# RFM69PI.net
KiCad netlist of a schematic drawn in EAGLE
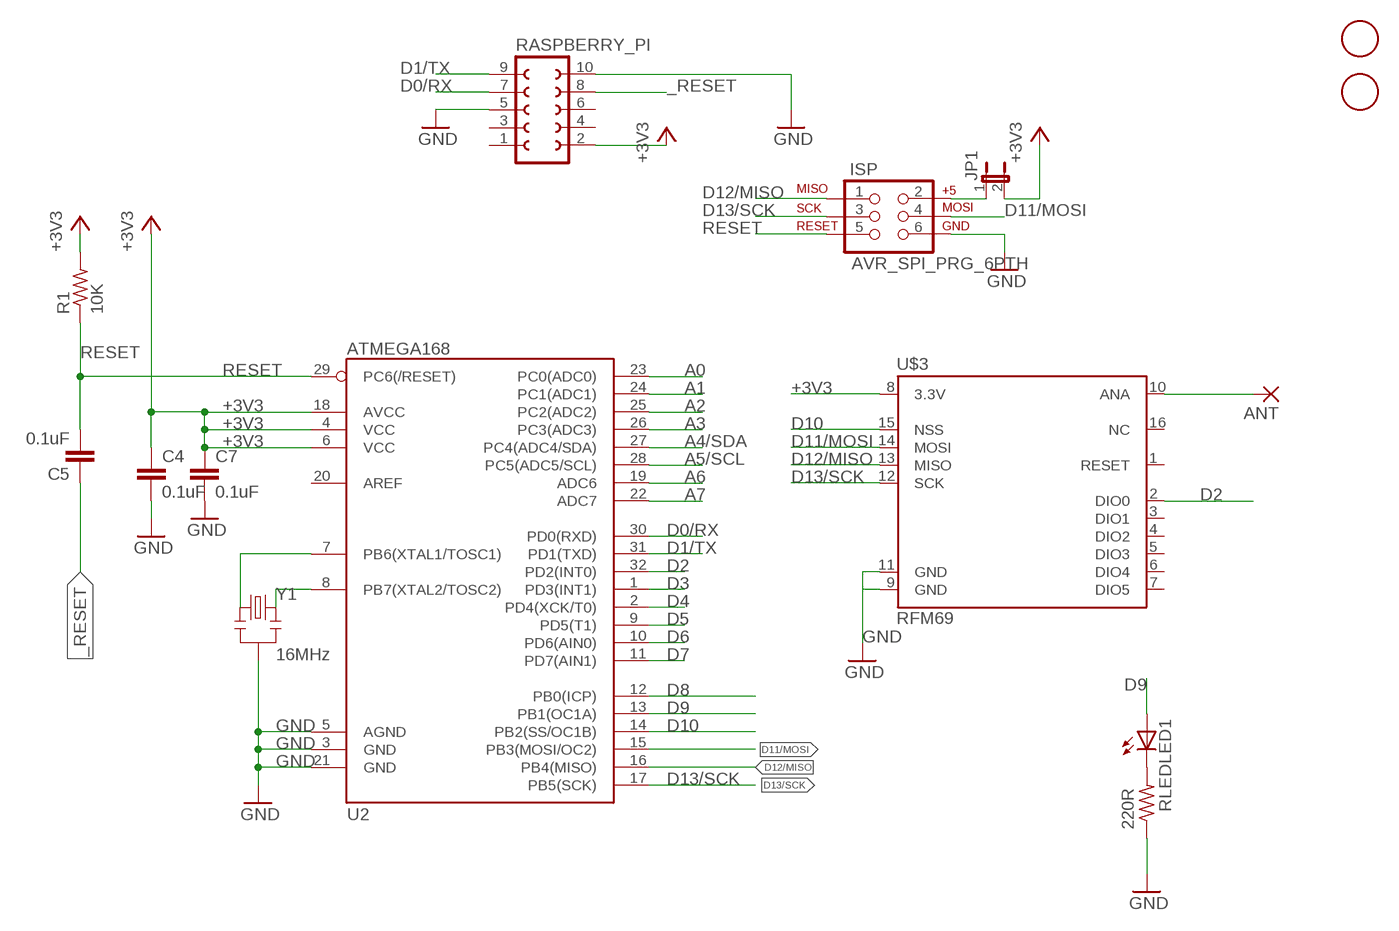
[diagram p0: schematic, sheet 1]

(export (version "E")
  (design (tool "Eeschema 10.0.6"))
  (components
    (comp (ref "ANT")
      (value "1,6/0,8")
      (footprint "eagle-import:1,6_0,8")
      (libsource (lib "eagle-import") (part "1,6/0,8"))
    )
    (comp (ref "C4")
      (value "0.1uF")
      (footprint "eagle-import:C0805")
      (libsource (lib "eagle-import") (part "C-EUC0805"))
    )
    (comp (ref "C5")
      (value "0.1uF")
      (footprint "eagle-import:C0805")
      (libsource (lib "eagle-import") (part "C-EUC0805"))
    )
    (comp (ref "C7")
      (value "0.1uF")
      (footprint "eagle-import:C0805")
      (libsource (lib "eagle-import") (part "resistor_C-EUC0805"))
    )
    (comp (ref "ISP")
      (value "AVR_SPI_PRG_6PTH")
      (footprint "eagle-import:2X3")
      (libsource (lib "eagle-import") (part "AVR_SPI_PRG_6PTH"))
    )
    (comp (ref "JP1")
      (value "JUMPER-2PTH")
      (footprint "eagle-import:1X02")
      (libsource (lib "eagle-import") (part "JUMPER-2PTH"))
    )
    (comp (ref "LED1")
      (value "LEDSML0805")
      (footprint "eagle-import:SML0805")
      (libsource (lib "eagle-import") (part "LEDSML0805"))
    )
    (comp (ref "R1")
      (value "10K")
      (footprint "eagle-import:R0805")
      (libsource (lib "eagle-import") (part "R-US_R0805"))
    )
    (comp (ref "RASPBERRY_PI")
      (value "FE05-2")
      (footprint "eagle-import:FE05-2")
      (libsource (lib "eagle-import") (part "FE05-2"))
    )
    (comp (ref "RLED")
      (value "220R")
      (footprint "eagle-import:R0805")
      (libsource (lib "eagle-import") (part "R-US_R0805"))
    )
    (comp (ref "U$1")
      (value "FIDUCIAL")
      (footprint "eagle-import:FIDUCIAL_1MM")
      (libsource (lib "eagle-import") (part "FIDUCIAL"))
    )
    (comp (ref "U$2")
      (value "FIDUCIAL")
      (footprint "eagle-import:FIDUCIAL_1MM")
      (libsource (lib "eagle-import") (part "FIDUCIAL"))
    )
    (comp (ref "U$3")
      (value "RFM69")
      (footprint "eagle-import:RFM69SMD")
      (libsource (lib "eagle-import") (part "RFM69"))
    )
    (comp (ref "U2")
      (value "ATMEGA168")
      (footprint "eagle-import:TQFP32-08")
      (libsource (lib "eagle-import") (part "ATMEGA168"))
    )
    (comp (ref "Y1")
      (value "16MHz")
      (footprint "eagle-import:RESONATOR-SMD")
      (libsource (lib "eagle-import") (part "RESONATOR16MHZ"))
    )
  )
  (nets
    (net (code "1") (name "+3V3") (class "Default")
      (node (ref "C4") (pin "1") (pinfunction "1_1") (pintype "passive"))
      (node (ref "C7") (pin "1") (pinfunction "1_1") (pintype "passive"))
      (node (ref "JP1") (pin "2") (pinfunction "2_2") (pintype "passive"))
      (node (ref "R1") (pin "2") (pinfunction "2_2") (pintype "passive"))
      (node (ref "RASPBERRY_PI") (pin "2") (pinfunction "2_2") (pintype "passive"))
      (node (ref "U$3") (pin "8") (pinfunction "3.3V_8") (pintype "power_in"))
      (node (ref "U2") (pin "18") (pinfunction "AVCC_18") (pintype "bidirectional"))
      (node (ref "U2") (pin "4") (pinfunction "VCC_4") (pintype "bidirectional"))
      (node (ref "U2") (pin "6") (pinfunction "VCC_6") (pintype "bidirectional"))
    )
    (net (code "2") (name "/A0") (class "Default")
      (node (ref "U2") (pin "23") (pinfunction "PC0(ADC0)_23") (pintype "bidirectional"))
    )
    (net (code "3") (name "/A1") (class "Default")
      (node (ref "U2") (pin "24") (pinfunction "PC1(ADC1)_24") (pintype "bidirectional"))
    )
    (net (code "4") (name "/A2") (class "Default")
      (node (ref "U2") (pin "25") (pinfunction "PC2(ADC2)_25") (pintype "bidirectional"))
    )
    (net (code "5") (name "/A3") (class "Default")
      (node (ref "U2") (pin "26") (pinfunction "PC3(ADC3)_26") (pintype "bidirectional"))
    )
    (net (code "6") (name "/A4{slash}SDA") (class "Default")
      (node (ref "U2") (pin "27") (pinfunction "PC4(ADC4/SDA)_27") (pintype "bidirectional"))
    )
    (net (code "7") (name "/A5{slash}SCL") (class "Default")
      (node (ref "U2") (pin "28") (pinfunction "PC5(ADC5/SCL)_28") (pintype "bidirectional"))
    )
    (net (code "8") (name "/A6") (class "Default")
      (node (ref "U2") (pin "19") (pinfunction "ADC6_19") (pintype "bidirectional"))
    )
    (net (code "9") (name "/A7") (class "Default")
      (node (ref "U2") (pin "22") (pinfunction "ADC7_22") (pintype "bidirectional"))
    )
    (net (code "10") (name "/D0{slash}RX") (class "Default")
      (node (ref "RASPBERRY_PI") (pin "7") (pinfunction "7_7") (pintype "passive"))
      (node (ref "U2") (pin "30") (pinfunction "PD0(RXD)_30") (pintype "bidirectional"))
    )
    (net (code "11") (name "/D1{slash}TX") (class "Default")
      (node (ref "RASPBERRY_PI") (pin "9") (pinfunction "9_9") (pintype "passive"))
      (node (ref "U2") (pin "31") (pinfunction "PD1(TXD)_31") (pintype "bidirectional"))
    )
    (net (code "12") (name "/D2") (class "Default")
      (node (ref "U$3") (pin "2") (pinfunction "DIO0_2") (pintype "bidirectional"))
      (node (ref "U2") (pin "32") (pinfunction "PD2(INT0)_32") (pintype "bidirectional"))
    )
    (net (code "13") (name "/D3") (class "Default")
      (node (ref "U2") (pin "1") (pinfunction "PD3(INT1)_1") (pintype "bidirectional"))
    )
    (net (code "14") (name "/D4") (class "Default")
      (node (ref "U2") (pin "2") (pinfunction "PD4(XCK/T0)_2") (pintype "bidirectional"))
    )
    (net (code "15") (name "/D5") (class "Default")
      (node (ref "U2") (pin "9") (pinfunction "PD5(T1)_9") (pintype "bidirectional"))
    )
    (net (code "16") (name "/D6") (class "Default")
      (node (ref "U2") (pin "10") (pinfunction "PD6(AIN0)_10") (pintype "bidirectional"))
    )
    (net (code "17") (name "/D7") (class "Default")
      (node (ref "U2") (pin "11") (pinfunction "PD7(AIN1)_11") (pintype "bidirectional"))
    )
    (net (code "18") (name "/D8") (class "Default")
      (node (ref "U2") (pin "12") (pinfunction "PB0(ICP)_12") (pintype "bidirectional"))
    )
    (net (code "19") (name "/D9") (class "Default")
      (node (ref "LED1") (pin "A") (pinfunction "A_A") (pintype "passive"))
      (node (ref "U2") (pin "13") (pinfunction "PB1(OC1A)_13") (pintype "bidirectional"))
    )
    (net (code "20") (name "/D10") (class "Default")
      (node (ref "U$3") (pin "15") (pinfunction "NSS_15") (pintype "input"))
      (node (ref "U2") (pin "14") (pinfunction "PB2(SS/OC1B)_14") (pintype "bidirectional"))
    )
    (net (code "21") (name "/NC") (class "Default")
      (node (ref "U$3") (pin "16") (pinfunction "NC_16") (pintype "power_in"))
    )
    (net (code "22") (name "/RESET") (class "Default")
      (node (ref "C5") (pin "2") (pinfunction "2_2") (pintype "passive"))
      (node (ref "ISP") (pin "5") (pinfunction "5_5") (pintype "passive"))
      (node (ref "R1") (pin "1") (pinfunction "1_1") (pintype "passive"))
      (node (ref "U2") (pin "29") (pinfunction "PC6(/RESET)_29") (pintype "bidirectional"))
    )
    (net (code "23") (name "D11{slash}MOSI") (class "Default")
      (node (ref "ISP") (pin "4") (pinfunction "4_4") (pintype "passive"))
      (node (ref "U$3") (pin "14") (pinfunction "MOSI_14") (pintype "input"))
      (node (ref "U2") (pin "15") (pinfunction "PB3(MOSI/OC2)_15") (pintype "bidirectional"))
    )
    (net (code "24") (name "D12{slash}MISO") (class "Default")
      (node (ref "ISP") (pin "1") (pinfunction "1_1") (pintype "passive"))
      (node (ref "U$3") (pin "13") (pinfunction "MISO_13") (pintype "output"))
      (node (ref "U2") (pin "16") (pinfunction "PB4(MISO)_16") (pintype "bidirectional"))
    )
    (net (code "25") (name "D13{slash}SCK") (class "Default")
      (node (ref "ISP") (pin "3") (pinfunction "3_3") (pintype "passive"))
      (node (ref "U$3") (pin "12") (pinfunction "SCK_12") (pintype "input"))
      (node (ref "U2") (pin "17") (pinfunction "PB5(SCK)_17") (pintype "bidirectional"))
    )
    (net (code "26") (name "GND") (class "Default")
      (node (ref "C4") (pin "2") (pinfunction "2_2") (pintype "passive"))
      (node (ref "C7") (pin "2") (pinfunction "2_2") (pintype "passive"))
      (node (ref "ISP") (pin "6") (pinfunction "6_6") (pintype "passive"))
      (node (ref "RASPBERRY_PI") (pin "10") (pinfunction "10_10") (pintype "passive"))
      (node (ref "RASPBERRY_PI") (pin "5") (pinfunction "5_5") (pintype "passive"))
      (node (ref "RLED") (pin "1") (pinfunction "1_1") (pintype "passive"))
      (node (ref "U$3") (pin "11") (pinfunction "GND_11") (pintype "power_in"))
      (node (ref "U$3") (pin "9") (pinfunction "GND_9") (pintype "power_in"))
      (node (ref "U2") (pin "21") (pinfunction "GND_21") (pintype "bidirectional"))
      (node (ref "U2") (pin "3") (pinfunction "GND_3") (pintype "bidirectional"))
      (node (ref "U2") (pin "5") (pinfunction "AGND_5") (pintype "bidirectional"))
      (node (ref "Y1") (pin "2") (pinfunction "2_2") (pintype "passive"))
    )
    (net (code "27") (name "Net-(ANT-P)") (class "Default")
      (node (ref "ANT") (pin "1") (pinfunction "P_1") (pintype "passive"))
      (node (ref "U$3") (pin "10") (pinfunction "ANA_10") (pintype "bidirectional"))
    )
    (net (code "28") (name "Net-(ISP-Pad2)") (class "Default")
      (node (ref "ISP") (pin "2") (pinfunction "2_2") (pintype "passive"))
      (node (ref "JP1") (pin "1") (pinfunction "1_1") (pintype "passive"))
    )
    (net (code "29") (name "Net-(LED1-PadC)") (class "Default")
      (node (ref "LED1") (pin "C") (pinfunction "C_C") (pintype "passive"))
      (node (ref "RLED") (pin "2") (pinfunction "2_2") (pintype "passive"))
    )
    (net (code "30") (name "Net-(U2-PB6(XTAL1{slash}TOSC1))") (class "Default")
      (node (ref "U2") (pin "7") (pinfunction "PB6(XTAL1/TOSC1)_7") (pintype "bidirectional"))
      (node (ref "Y1") (pin "1") (pinfunction "1_1") (pintype "passive"))
    )
    (net (code "31") (name "Net-(U2-PB7(XTAL2{slash}TOSC2))") (class "Default")
      (node (ref "U2") (pin "8") (pinfunction "PB7(XTAL2/TOSC2)_8") (pintype "bidirectional"))
      (node (ref "Y1") (pin "3") (pinfunction "3_3") (pintype "passive"))
    )
    (net (code "32") (name "_RESET") (class "Default")
      (node (ref "C5") (pin "1") (pinfunction "1_1") (pintype "passive"))
      (node (ref "RASPBERRY_PI") (pin "8") (pinfunction "8_8") (pintype "passive"))
    )
    (net (code "33") (name "unconnected-(RASPBERRY_PI-Pad1)") (class "Default")
      (node (ref "RASPBERRY_PI") (pin "1") (pinfunction "1_1") (pintype "passive"))
    )
    (net (code "34") (name "unconnected-(RASPBERRY_PI-Pad3)") (class "Default")
      (node (ref "RASPBERRY_PI") (pin "3") (pinfunction "3_3") (pintype "passive"))
    )
    (net (code "35") (name "unconnected-(RASPBERRY_PI-Pad4)") (class "Default")
      (node (ref "RASPBERRY_PI") (pin "4") (pinfunction "4_4") (pintype "passive"))
    )
    (net (code "36") (name "unconnected-(RASPBERRY_PI-Pad6)") (class "Default")
      (node (ref "RASPBERRY_PI") (pin "6") (pinfunction "6_6") (pintype "passive"))
    )
    (net (code "37") (name "unconnected-(U$3-DIO1-Pad3)") (class "Default")
      (node (ref "U$3") (pin "3") (pinfunction "DIO1_3") (pintype "bidirectional"))
    )
    (net (code "38") (name "unconnected-(U$3-DIO2-Pad4)") (class "Default")
      (node (ref "U$3") (pin "4") (pinfunction "DIO2_4") (pintype "bidirectional"))
    )
    (net (code "39") (name "unconnected-(U$3-DIO3-Pad5)") (class "Default")
      (node (ref "U$3") (pin "5") (pinfunction "DIO3_5") (pintype "bidirectional"))
    )
    (net (code "40") (name "unconnected-(U$3-DIO4-Pad6)") (class "Default")
      (node (ref "U$3") (pin "6") (pinfunction "DIO4_6") (pintype "bidirectional"))
    )
    (net (code "41") (name "unconnected-(U$3-DIO5-Pad7)") (class "Default")
      (node (ref "U$3") (pin "7") (pinfunction "DIO5_7") (pintype "bidirectional"))
    )
    (net (code "42") (name "unconnected-(U$3-RESET-Pad1)") (class "Default")
      (node (ref "U$3") (pin "1") (pinfunction "RESET_1") (pintype "input"))
    )
    (net (code "43") (name "unconnected-(U2-AREF-Pad20)") (class "Default")
      (node (ref "U2") (pin "20") (pinfunction "AREF_20") (pintype "bidirectional"))
    )
  )
)
